# Schematic.net
KiCad netlist of a schematic drawn in EAGLE
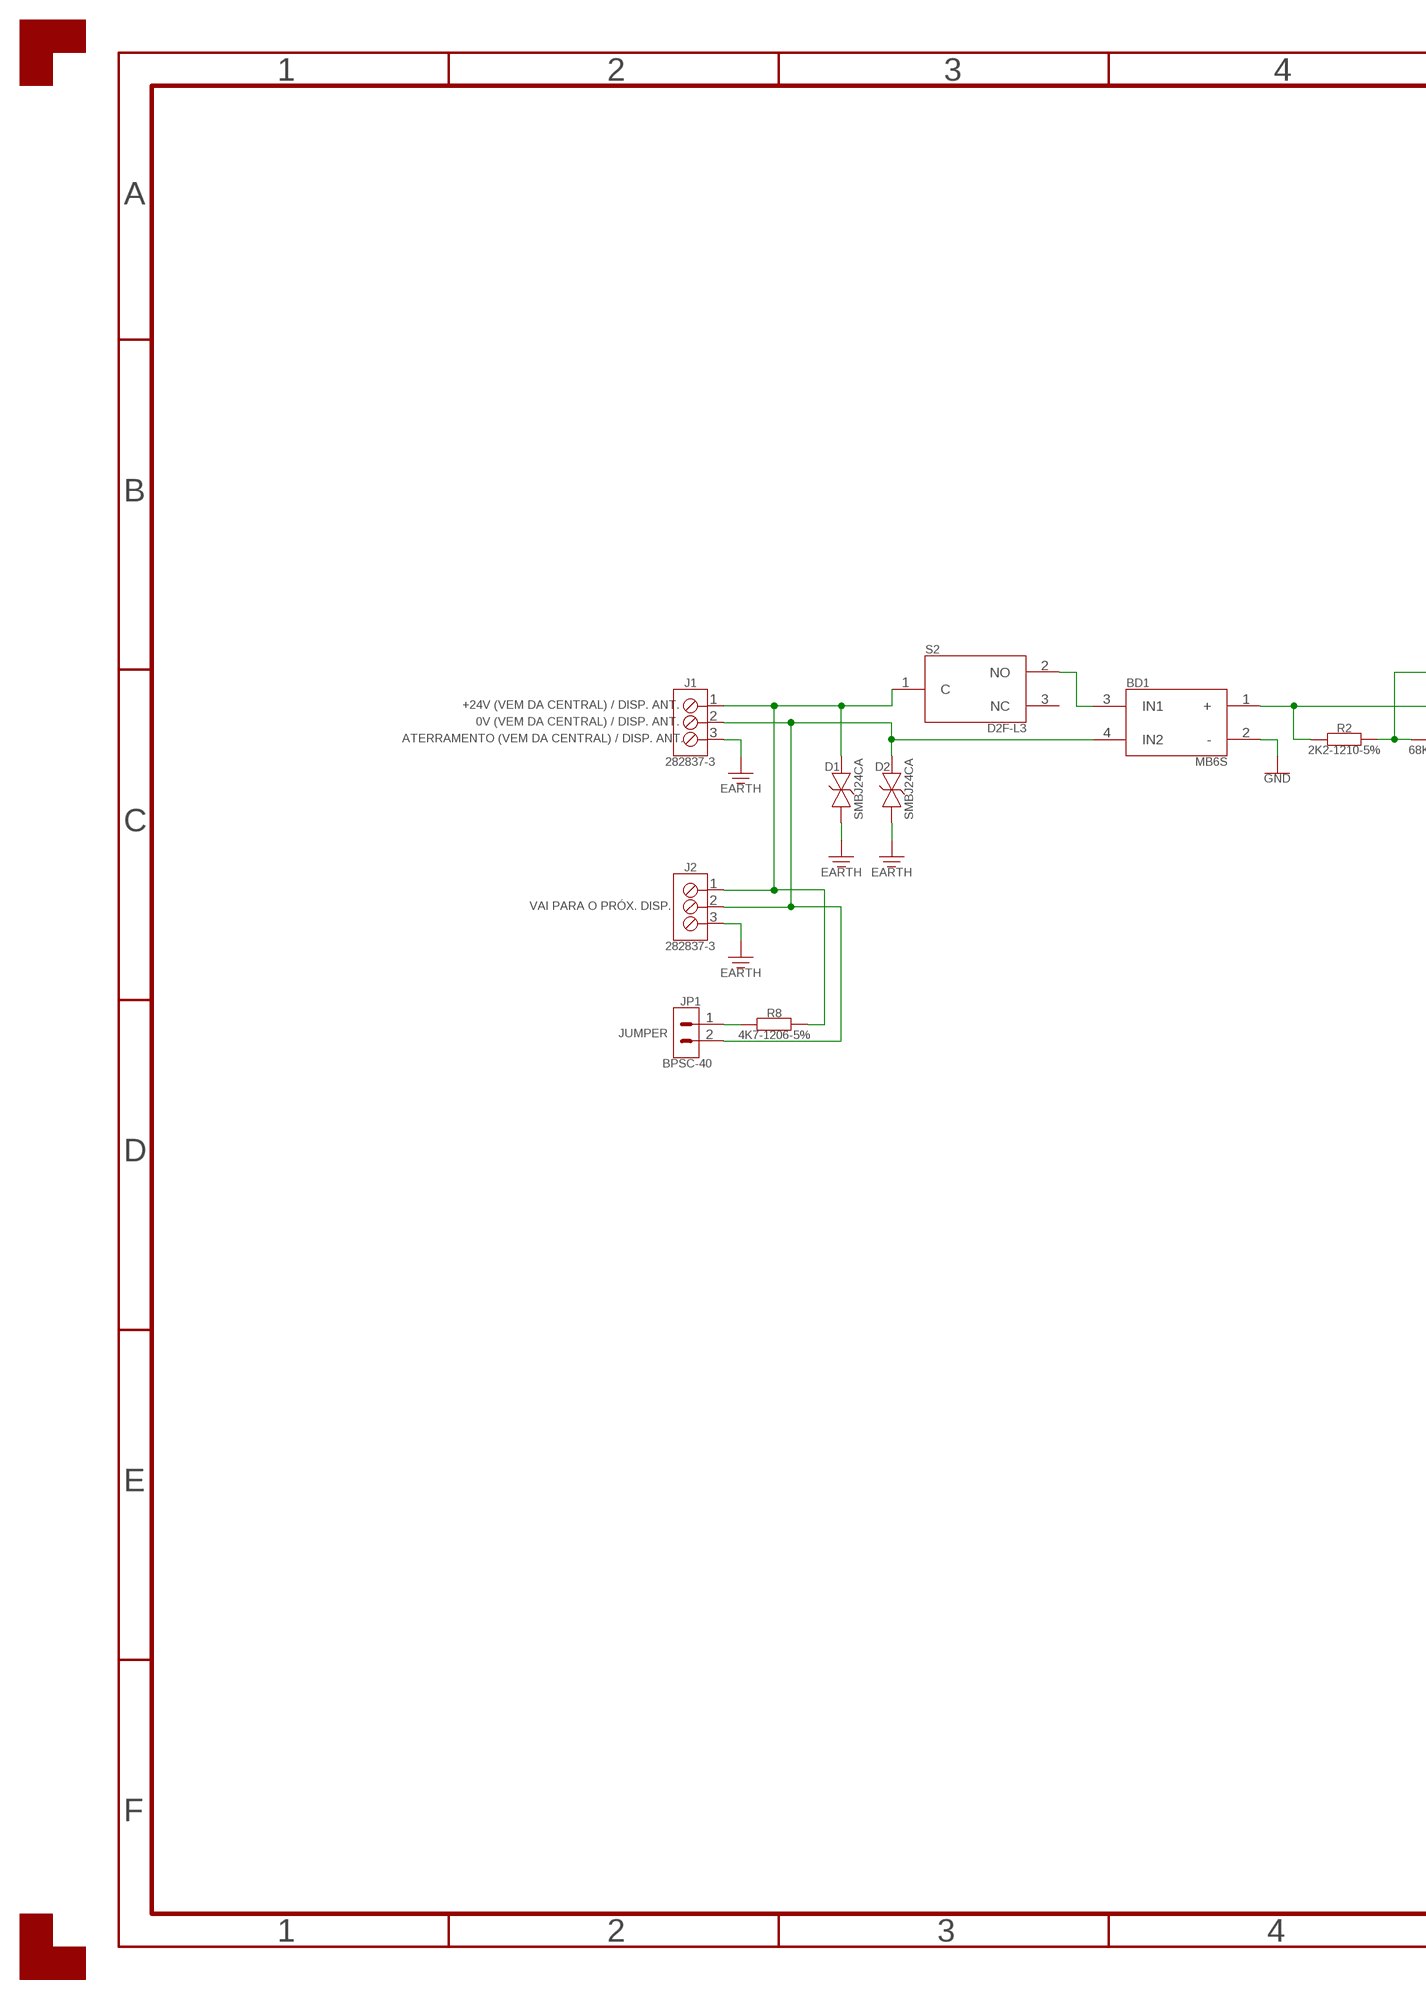
[diagram p0: schematic, sheet 1, part 1 of 2]
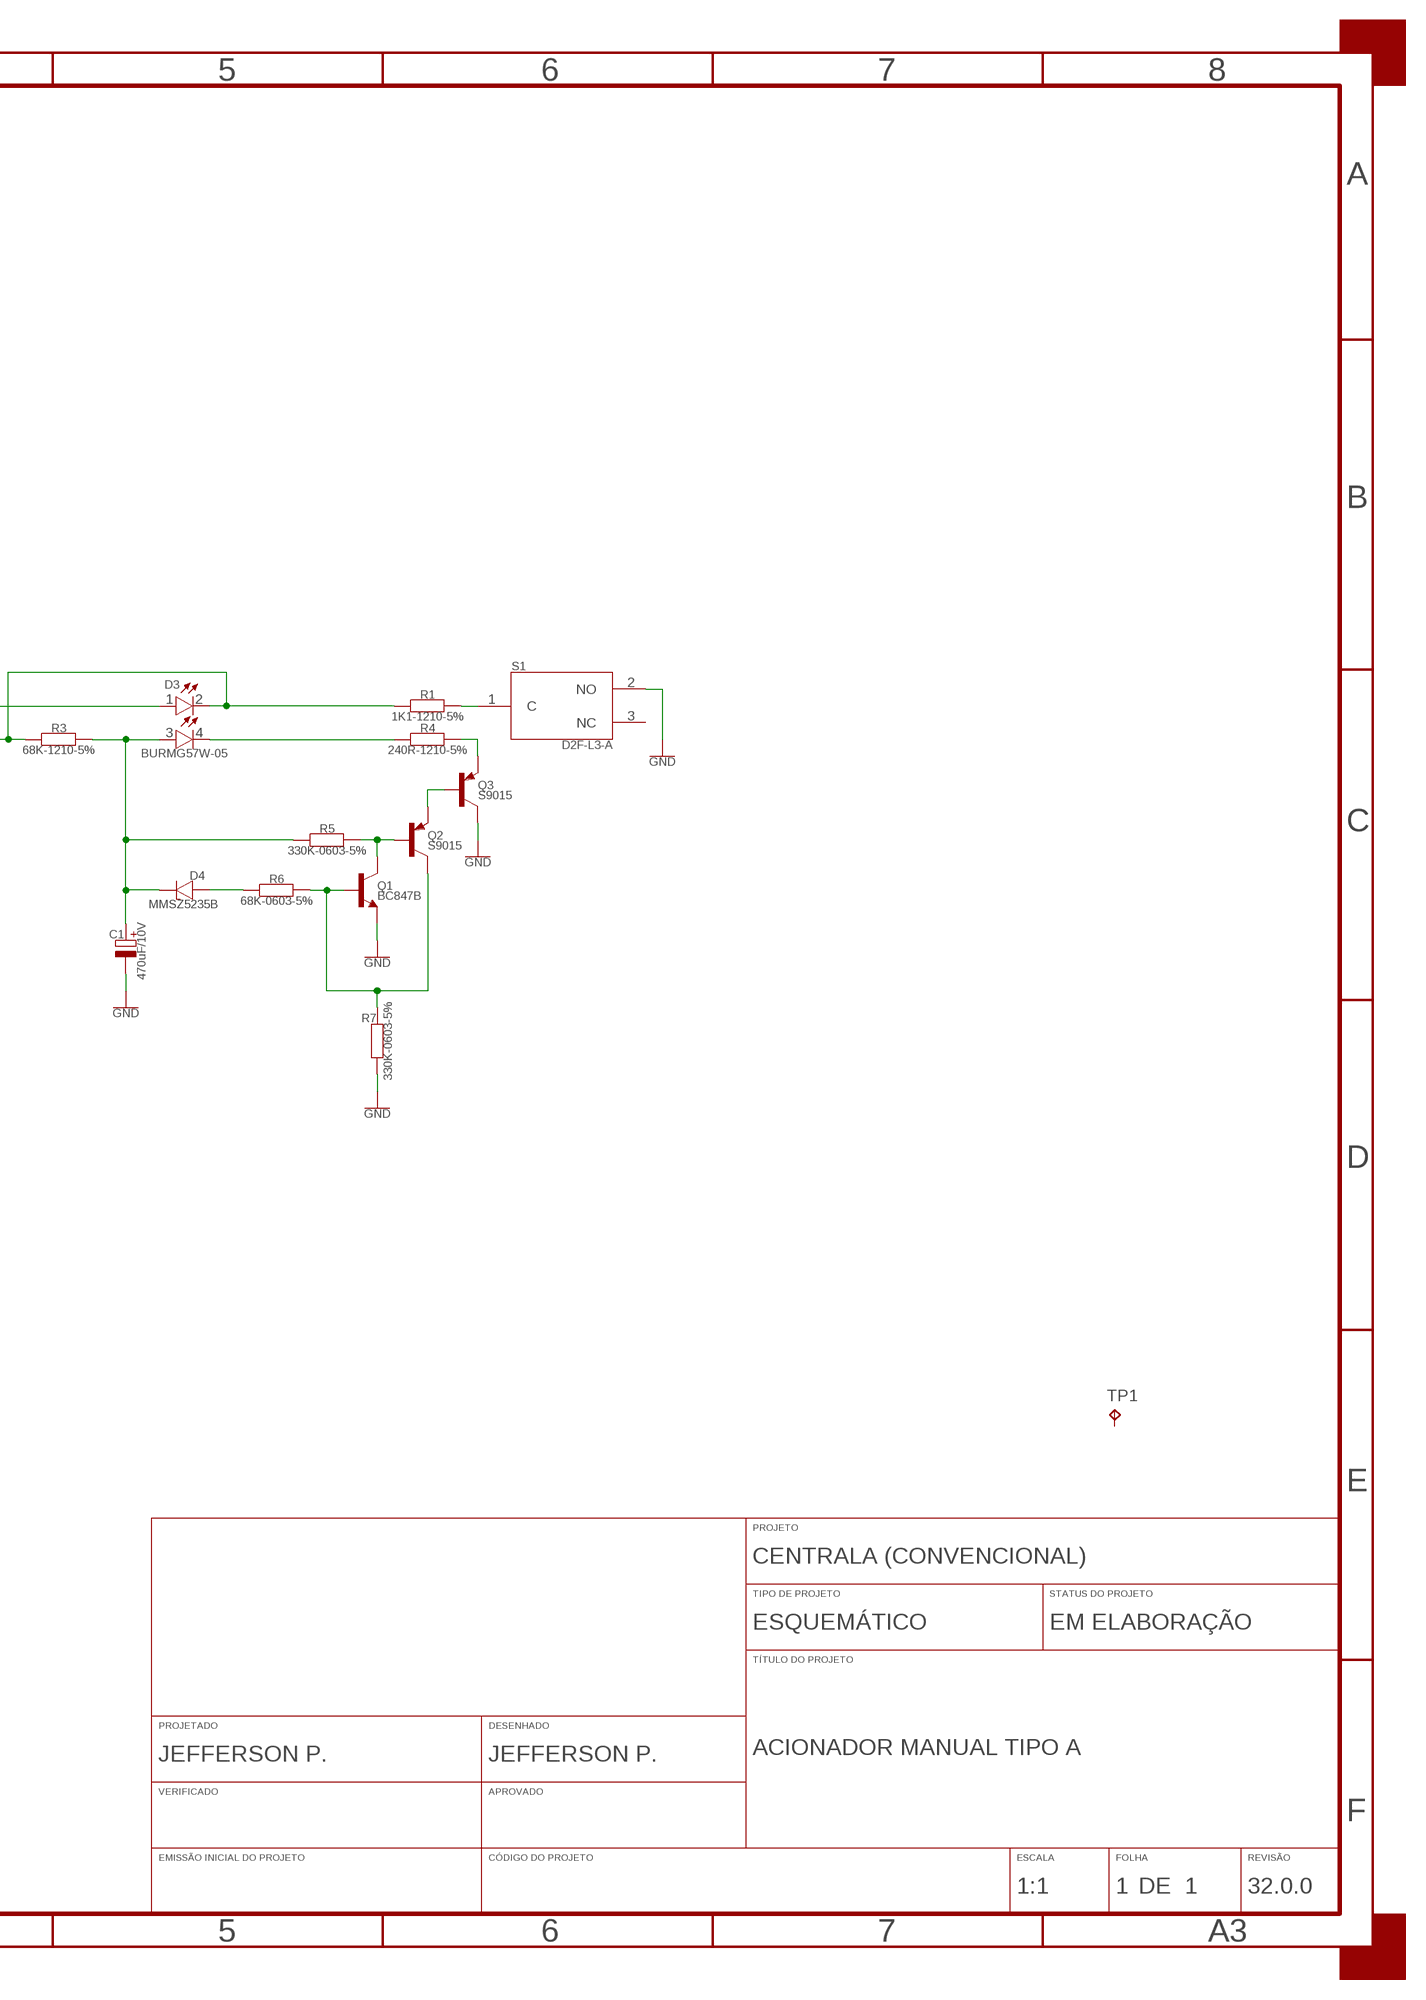
[diagram p1: schematic, sheet 1, part 2 of 2]

(export (version "E")
  (design (tool "Eeschema 10.0.6"))
  (components
    (comp (ref "BD1")
      (value "MB6S")
      (footprint "eagle-import:SOIC-4W")
      (fields (field (name "MANUFACTURER") "Semiconductor Components Industries"))
      (libsource (lib "eagle-import") (part "MB6SMB6S"))
    )
    (comp (ref "C1")
      (value "470uF/10V")
      (footprint "eagle-import:CAPAE830X1050N")
      (libsource (lib "eagle-import") (part "C-POLECAP-8.5MM_"))
    )
    (comp (ref "D1")
      (value "SMBJ24CA")
      (footprint "eagle-import:DO-214AA")
      (fields (field (name "MANUFACTURER") "Littelfuse, Inc."))
      (libsource (lib "eagle-import") (part "SMBJ24CASMBJ24CA"))
    )
    (comp (ref "D2")
      (value "SMBJ24CA")
      (footprint "eagle-import:DO-214AA")
      (fields (field (name "MANUFACTURER") "Littelfuse, Inc."))
      (libsource (lib "eagle-import") (part "SMBJ24CASMBJ24CA"))
    )
    (comp (ref "D3")
      (value "BURMG57W-05")
      (footprint "eagle-import:BI-1206")
      (fields (field (name "MANUFACTURER") "NICOMATIC"))
      (libsource (lib "eagle-import") (part "BURMG57W-05BURMG57W-05"))
    )
    (comp (ref "D4")
      (value "MMSZ5235B")
      (footprint "eagle-import:SOD-123-2")
      (fields (field (name "MANUFACTURER") "Vishay"))
      (libsource (lib "eagle-import") (part "MMSZ5235B-E3-08MMSZ5235B-E3-08"))
    )
    (comp (ref "J1")
      (value "282837-3")
      (footprint "eagle-import:TERMBLK_508-3N")
      (fields (field (name "MANUFACTURER") "TE Connectivity AMP Connectors"))
      (libsource (lib "eagle-import") (part "2828XX-3282837-3"))
    )
    (comp (ref "J2")
      (value "282837-3")
      (footprint "eagle-import:TERMBLK_508-3N")
      (fields (field (name "MANUFACTURER") "TE Connectivity AMP Connectors"))
      (libsource (lib "eagle-import") (part "2828XX-3282837-3"))
    )
    (comp (ref "JP1")
      (value "BPSC-40")
      (footprint "eagle-import:1X02")
      (libsource (lib "eagle-import") (part "PINHD-1X2"))
    )
    (comp (ref "Q1")
      (value "BC847B")
      (footprint "eagle-import:SOT23-3")
      (fields (field (name "MANUFACTURER") "Nexperia B.V."))
      (libsource (lib "eagle-import") (part "BC847BBC847B"))
    )
    (comp (ref "Q2")
      (value "S9015")
      (footprint "eagle-import:SOT23-3")
      (fields (field (name "MANUFACTURER") "Secos Elektronische Bauelemente"))
      (libsource (lib "eagle-import") (part "S9015S9015"))
    )
    (comp (ref "Q3")
      (value "S9015")
      (footprint "eagle-import:SOT23-3")
      (fields (field (name "MANUFACTURER") "Secos Elektronische Bauelemente"))
      (libsource (lib "eagle-import") (part "S9015S9015"))
    )
    (comp (ref "R1")
      (value "1K1-1210-5%")
      (footprint "eagle-import:RESC3224X71")
      (libsource (lib "eagle-import") (part "RCHIP-1210(3225-METRIC)_"))
    )
    (comp (ref "R2")
      (value "2K2-1210-5%")
      (footprint "eagle-import:RESC3224X71")
      (libsource (lib "eagle-import") (part "RCHIP-1210(3225-METRIC)_"))
    )
    (comp (ref "R3")
      (value "68K-1210-5%")
      (footprint "eagle-import:RESC3224X71")
      (libsource (lib "eagle-import") (part "RCHIP-1210(3225-METRIC)_"))
    )
    (comp (ref "R4")
      (value "240R-1210-5%")
      (footprint "eagle-import:RESC3224X71")
      (libsource (lib "eagle-import") (part "RCHIP-1210(3225-METRIC)_"))
    )
    (comp (ref "R5")
      (value "330K-0603-5%")
      (footprint "eagle-import:RESC1608X60")
      (libsource (lib "eagle-import") (part "RCHIP-0603(1608-METRIC)_"))
    )
    (comp (ref "R6")
      (value "68K-0603-5%")
      (footprint "eagle-import:RESC1608X60")
      (libsource (lib "eagle-import") (part "RCHIP-0603(1608-METRIC)_"))
    )
    (comp (ref "R7")
      (value "330K-0603-5%")
      (footprint "eagle-import:RESC1608X60")
      (libsource (lib "eagle-import") (part "RCHIP-0603(1608-METRIC)_"))
    )
    (comp (ref "R8")
      (value "4K7-1206-5%")
      (footprint "eagle-import:RESC3216X70")
      (libsource (lib "eagle-import") (part "RCHIP-1206(3216-METRIC)_"))
    )
    (comp (ref "S1")
      (value "D2F-L3-A")
      (footprint "eagle-import:D2F-L3-A")
      (fields (field (name "MANUFACTURER") "OMRON Corporation"))
      (libsource (lib "eagle-import") (part "D2F-L3-AD2F-L3-A"))
    )
    (comp (ref "S2")
      (value "D2F-L3")
      (footprint "eagle-import:D2F-L3")
      (fields (field (name "MANUFACTURER") "OMRON Corporation"))
      (libsource (lib "eagle-import") (part "D2F-L3D2F-L3"))
    )
    (comp (ref "TP1")
      (value "TPTP16R")
      (footprint "eagle-import:TP16R")
      (libsource (lib "eagle-import") (part "TPTP16R"))
    )
  )
  (nets
    (net (code "1") (name "EARTH") (class "Default")
      (node (ref "D1") (pin "A") (pinfunction "1_A") (pintype "passive"))
      (node (ref "D2") (pin "A") (pinfunction "1_A") (pintype "passive"))
      (node (ref "J1") (pin "3") (pinfunction "3_3") (pintype "bidirectional"))
      (node (ref "J2") (pin "3") (pinfunction "3_3") (pintype "bidirectional"))
    )
    (net (code "2") (name "GND") (class "Default")
      (node (ref "BD1") (pin "2") (pinfunction "-_2") (pintype "output"))
      (node (ref "C1") (pin "2") (pinfunction "-_2") (pintype "passive"))
      (node (ref "Q1") (pin "2") (pinfunction "E_2") (pintype "passive"))
      (node (ref "Q3") (pin "3") (pinfunction "C_3") (pintype "passive"))
      (node (ref "R7") (pin "1") (pinfunction "1_1") (pintype "passive"))
      (node (ref "S1") (pin "2") (pinfunction "NO_2") (pintype "passive"))
    )
    (net (code "3") (name "Net-(BD1-+)") (class "Default")
      (node (ref "BD1") (pin "1") (pinfunction "+_1") (pintype "output"))
      (node (ref "D3") (pin "1") (pinfunction "A1_1") (pintype "passive"))
      (node (ref "R2") (pin "1") (pinfunction "1_1") (pintype "passive"))
    )
    (net (code "4") (name "Net-(BD1-IN1)") (class "Default")
      (node (ref "BD1") (pin "3") (pinfunction "IN1_3") (pintype "input"))
      (node (ref "S2") (pin "2") (pinfunction "NO_2") (pintype "passive"))
    )
    (net (code "5") (name "Net-(BD1-IN2)") (class "Default")
      (node (ref "BD1") (pin "4") (pinfunction "IN2_4") (pintype "input"))
      (node (ref "D2") (pin "C") (pinfunction "2_C") (pintype "passive"))
      (node (ref "J1") (pin "2") (pinfunction "2_2") (pintype "bidirectional"))
      (node (ref "J2") (pin "2") (pinfunction "2_2") (pintype "bidirectional"))
      (node (ref "JP1") (pin "2") (pinfunction "2_2") (pintype "passive"))
    )
    (net (code "6") (name "Net-(C1-+)") (class "Default")
      (node (ref "C1") (pin "1") (pinfunction "+_1") (pintype "passive"))
      (node (ref "D3") (pin "3") (pinfunction "A3_3") (pintype "passive"))
      (node (ref "D4") (pin "C") (pinfunction "P$2_C") (pintype "passive"))
      (node (ref "R3") (pin "2") (pinfunction "2_2") (pintype "passive"))
      (node (ref "R5") (pin "1") (pinfunction "1_1") (pintype "passive"))
    )
    (net (code "7") (name "Net-(D1-2)") (class "Default")
      (node (ref "D1") (pin "C") (pinfunction "2_C") (pintype "passive"))
      (node (ref "J1") (pin "1") (pinfunction "1_1") (pintype "bidirectional"))
      (node (ref "J2") (pin "1") (pinfunction "1_1") (pintype "bidirectional"))
      (node (ref "R8") (pin "2") (pinfunction "2_2") (pintype "passive"))
      (node (ref "S2") (pin "1") (pinfunction "C_1") (pintype "passive"))
    )
    (net (code "8") (name "Net-(D3-C2)") (class "Default")
      (node (ref "D3") (pin "2") (pinfunction "C2_2") (pintype "passive"))
      (node (ref "R1") (pin "1") (pinfunction "1_1") (pintype "passive"))
      (node (ref "R2") (pin "2") (pinfunction "2_2") (pintype "passive"))
      (node (ref "R3") (pin "1") (pinfunction "1_1") (pintype "passive"))
    )
    (net (code "9") (name "Net-(D3-C4)") (class "Default")
      (node (ref "D3") (pin "4") (pinfunction "C4_4") (pintype "passive"))
      (node (ref "R4") (pin "1") (pinfunction "1_1") (pintype "passive"))
    )
    (net (code "10") (name "Net-(D4-P$1)") (class "Default")
      (node (ref "D4") (pin "A") (pinfunction "P$1_A") (pintype "passive"))
      (node (ref "R6") (pin "1") (pinfunction "1_1") (pintype "passive"))
    )
    (net (code "11") (name "Net-(JP1-Pad1)") (class "Default")
      (node (ref "JP1") (pin "1") (pinfunction "1_1") (pintype "passive"))
      (node (ref "R8") (pin "1") (pinfunction "1_1") (pintype "passive"))
    )
    (net (code "12") (name "Net-(Q1-B)") (class "Default")
      (node (ref "Q1") (pin "1") (pinfunction "B_1") (pintype "passive"))
      (node (ref "Q2") (pin "3") (pinfunction "C_3") (pintype "passive"))
      (node (ref "R6") (pin "2") (pinfunction "2_2") (pintype "passive"))
      (node (ref "R7") (pin "2") (pinfunction "2_2") (pintype "passive"))
    )
    (net (code "13") (name "Net-(Q1-C)") (class "Default")
      (node (ref "Q1") (pin "3") (pinfunction "C_3") (pintype "passive"))
      (node (ref "Q2") (pin "1") (pinfunction "B_1") (pintype "passive"))
      (node (ref "R5") (pin "2") (pinfunction "2_2") (pintype "passive"))
    )
    (net (code "14") (name "Net-(Q2-E)") (class "Default")
      (node (ref "Q2") (pin "2") (pinfunction "E_2") (pintype "passive"))
      (node (ref "Q3") (pin "1") (pinfunction "B_1") (pintype "passive"))
    )
    (net (code "15") (name "Net-(Q3-E)") (class "Default")
      (node (ref "Q3") (pin "2") (pinfunction "E_2") (pintype "passive"))
      (node (ref "R4") (pin "2") (pinfunction "2_2") (pintype "passive"))
    )
    (net (code "16") (name "Net-(S1-C)") (class "Default")
      (node (ref "R1") (pin "2") (pinfunction "2_2") (pintype "passive"))
      (node (ref "S1") (pin "1") (pinfunction "C_1") (pintype "passive"))
    )
    (net (code "17") (name "unconnected-(S1-NC-Pad3)") (class "Default")
      (node (ref "S1") (pin "3") (pinfunction "NC_3") (pintype "passive"))
    )
    (net (code "18") (name "unconnected-(S2-NC-Pad3)") (class "Default")
      (node (ref "S2") (pin "3") (pinfunction "NC_3") (pintype "passive"))
    )
    (net (code "19") (name "unconnected-(TP1-PadTP)") (class "Default")
      (node (ref "TP1") (pin "TP") (pinfunction "TP_TP") (pintype "input"))
    )
  )
)
